# Aquila-2018-Under.net
KiCad netlist of a schematic drawn in EAGLE
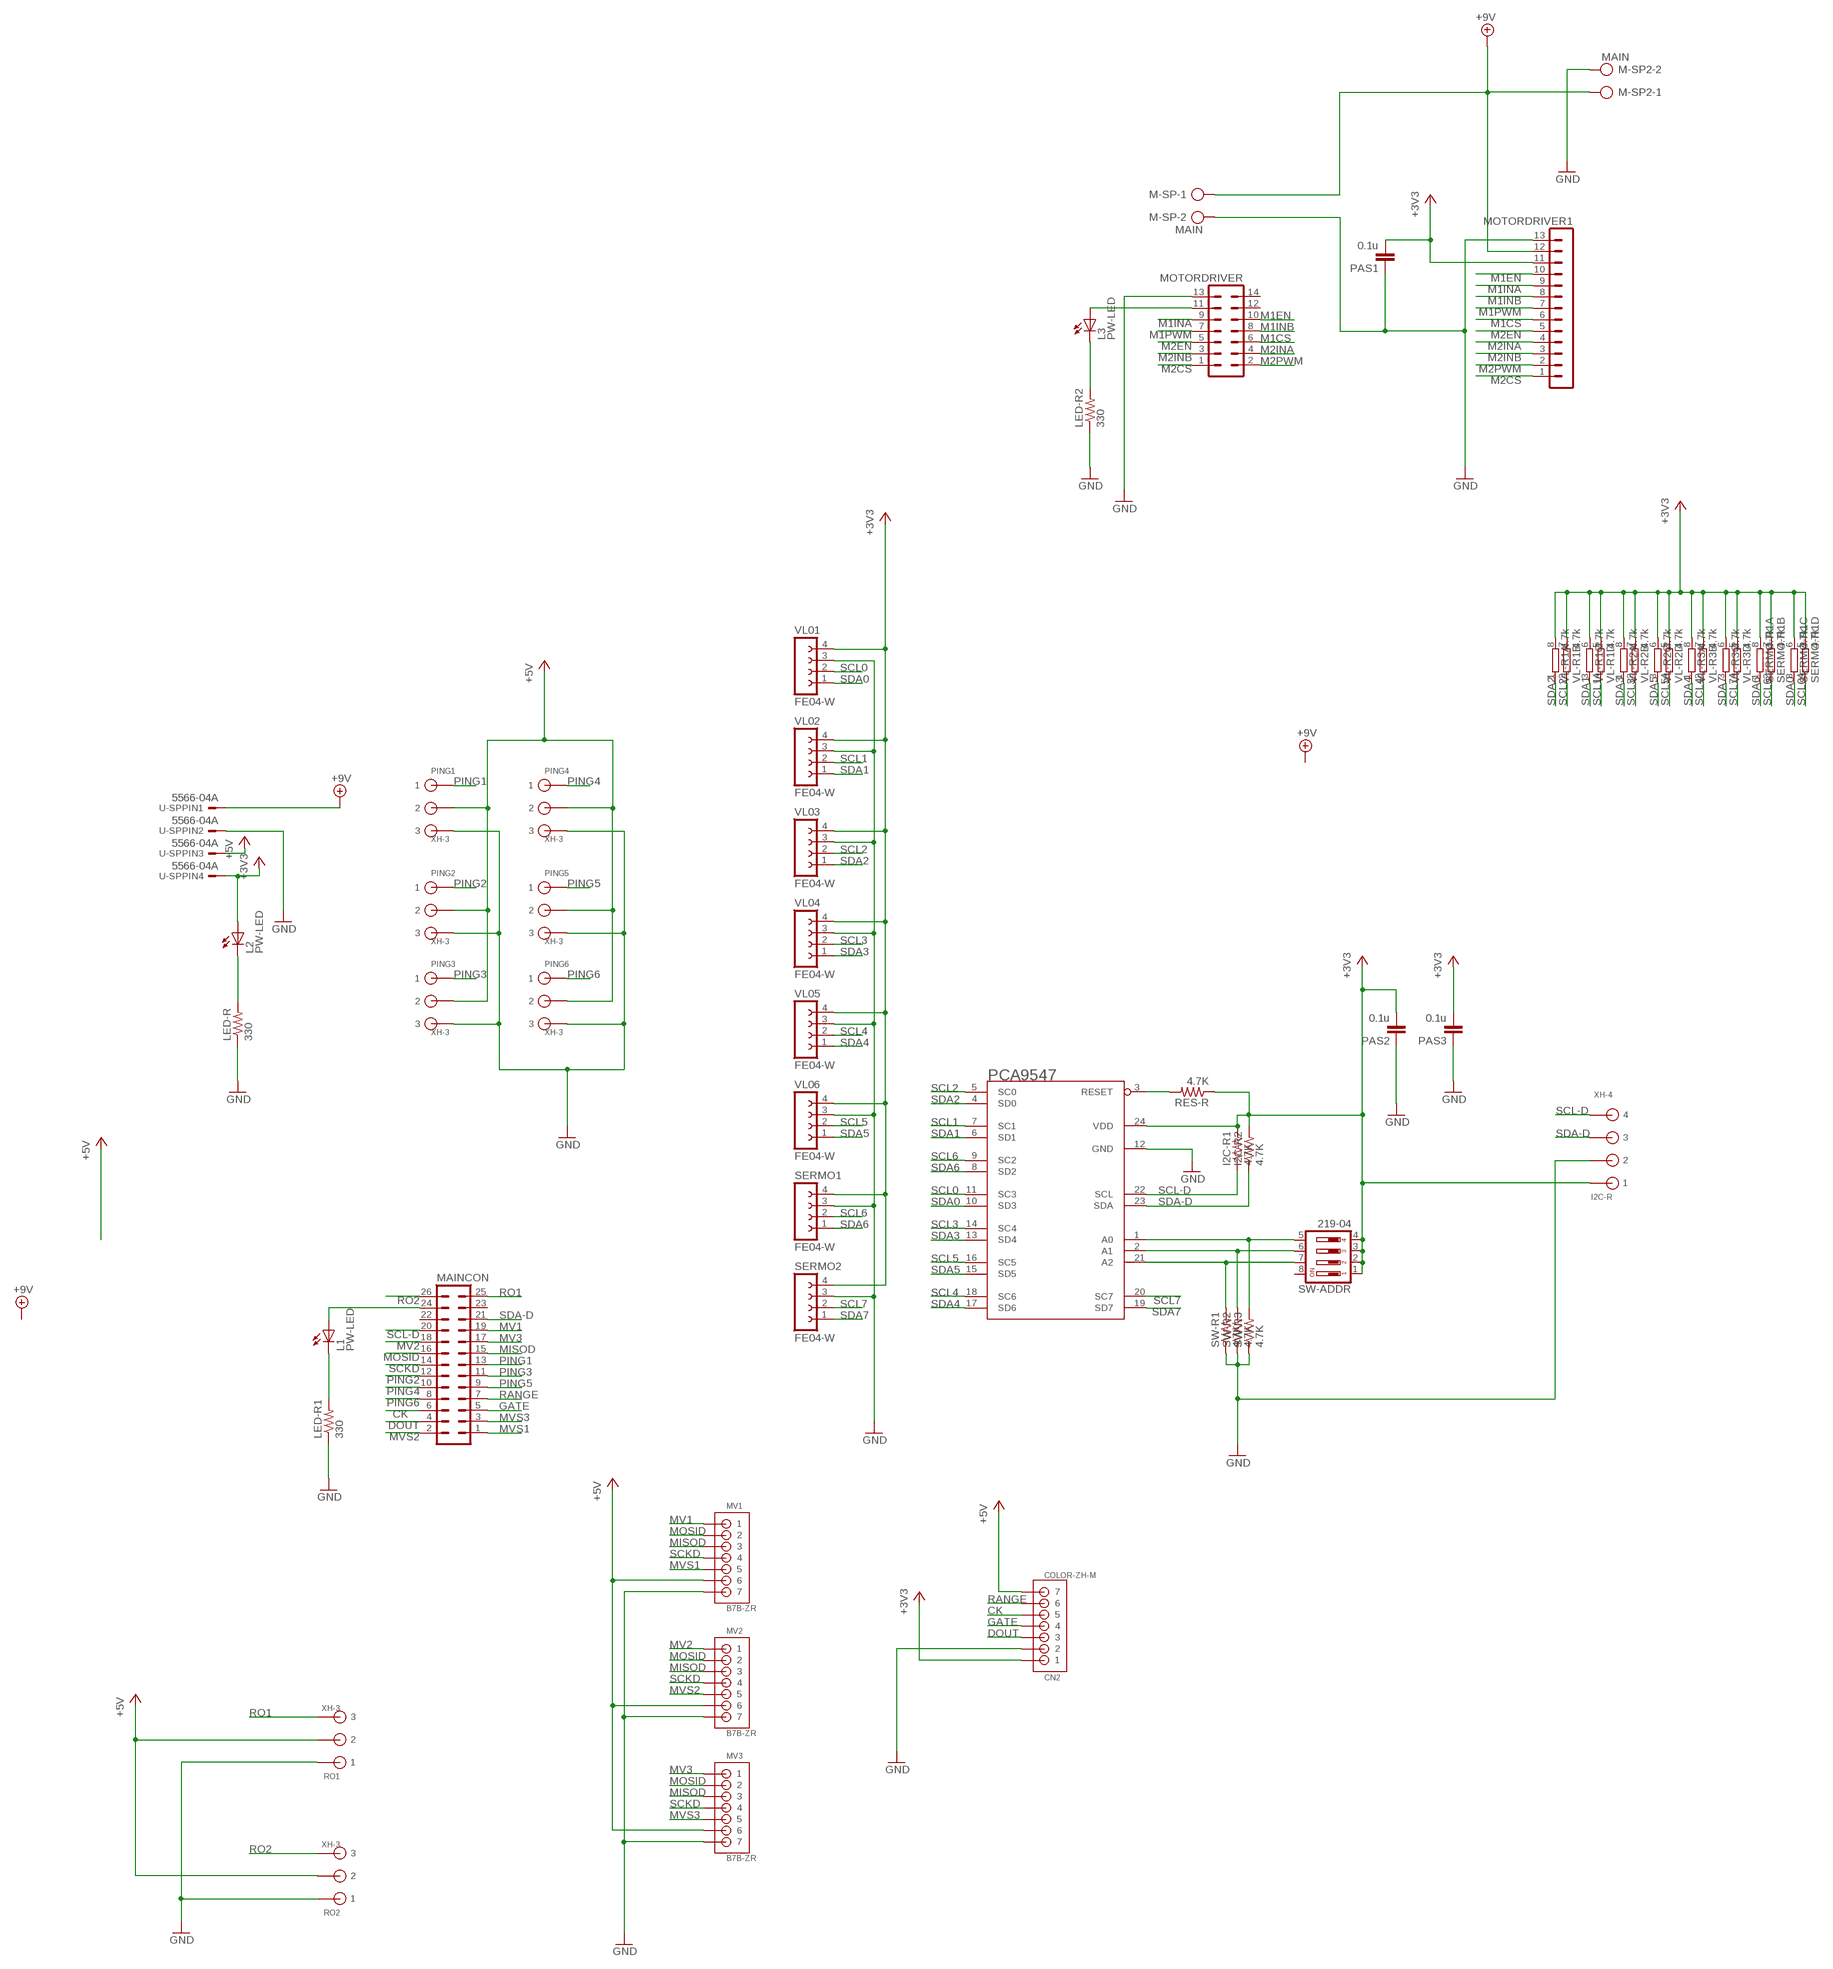
[diagram p0: schematic, sheet 1]

(export (version "E")
  (design (tool "Eeschema 10.0.6"))
  (components
    (comp (ref "CN2")
      (value "COLOR-ZH-M")
      (footprint "eagle-import:B7B-ZR")
      (libsource (lib "eagle-import") (part "B7B-ZR"))
    )
    (comp (ref "I2C-R")
      (value "XH-4")
      (footprint "eagle-import:CON4")
      (libsource (lib "eagle-import") (part "XH-4"))
    )
    (comp (ref "I2C-R1")
      (value "4.7K")
      (footprint "eagle-import:R0805")
      (libsource (lib "eagle-import") (part "R-US_R0805"))
    )
    (comp (ref "I2C-R2")
      (value "4.7K")
      (footprint "eagle-import:R0805")
      (libsource (lib "eagle-import") (part "R-US_R0805"))
    )
    (comp (ref "L1")
      (value "PW-LED")
      (footprint "eagle-import:CHIPLED_0805")
      (libsource (lib "eagle-import") (part "LEDCHIPLED_0805"))
    )
    (comp (ref "L2")
      (value "PW-LED")
      (footprint "eagle-import:CHIPLED_0805")
      (libsource (lib "eagle-import") (part "LEDCHIPLED_0805"))
    )
    (comp (ref "L3")
      (value "PW-LED")
      (footprint "eagle-import:CHIPLED_0805")
      (libsource (lib "eagle-import") (part "LEDCHIPLED_0805"))
    )
    (comp (ref "LED-R")
      (value "330")
      (footprint "eagle-import:R0805")
      (libsource (lib "eagle-import") (part "R-US_R0805"))
    )
    (comp (ref "LED-R1")
      (value "330")
      (footprint "eagle-import:R0805")
      (libsource (lib "eagle-import") (part "R-US_R0805"))
    )
    (comp (ref "LED-R2")
      (value "330")
      (footprint "eagle-import:R0805")
      (libsource (lib "eagle-import") (part "R-US_R0805"))
    )
    (comp (ref "M-SP")
      (value "MAIN")
      (footprint "eagle-import:AK500_2")
      (libsource (lib "eagle-import") (part "AK500/2"))
    )
    (comp (ref "M-SP2")
      (value "MAIN")
      (footprint "eagle-import:AK500_2")
      (libsource (lib "eagle-import") (part "AK500/2"))
    )
    (comp (ref "MAINCON")
      (value "ML26")
      (footprint "eagle-import:ML26")
      (libsource (lib "eagle-import") (part "ML26"))
    )
    (comp (ref "MOTORDRIVER")
      (value "ML14")
      (footprint "eagle-import:ML14")
      (libsource (lib "eagle-import") (part "ML14"))
    )
    (comp (ref "MOTORDRIVER1")
      (value "MA13-1")
      (footprint "eagle-import:MA13-1")
      (libsource (lib "eagle-import") (part "MA13-1"))
    )
    (comp (ref "MV1")
      (value "B7B-ZR")
      (footprint "eagle-import:B7B-ZR")
      (libsource (lib "eagle-import") (part "B7B-ZR"))
    )
    (comp (ref "MV2")
      (value "B7B-ZR")
      (footprint "eagle-import:B7B-ZR")
      (libsource (lib "eagle-import") (part "B7B-ZR"))
    )
    (comp (ref "MV3")
      (value "B7B-ZR")
      (footprint "eagle-import:B7B-ZR")
      (libsource (lib "eagle-import") (part "B7B-ZR"))
    )
    (comp (ref "PAS1")
      (value "0.1u")
      (footprint "eagle-import:C0805")
      (fields (field (name "SPICEPREFIX") "B"))
      (libsource (lib "eagle-import") (part "C-EUC0805"))
    )
    (comp (ref "PAS2")
      (value "0.1u")
      (footprint "eagle-import:C0805")
      (fields (field (name "SPICEPREFIX") "B"))
      (libsource (lib "eagle-import") (part "C-EUC0805"))
    )
    (comp (ref "PAS3")
      (value "0.1u")
      (footprint "eagle-import:C0805")
      (fields (field (name "SPICEPREFIX") "B"))
      (libsource (lib "eagle-import") (part "C-EUC0805"))
    )
    (comp (ref "PCA9547")
      (value "PCA9547")
      (footprint "eagle-import:SO24L")
      (libsource (lib "eagle-import") (part "PCA9547"))
    )
    (comp (ref "PING1")
      (value "XH-3")
      (footprint "eagle-import:CON3")
      (libsource (lib "eagle-import") (part "XH-3"))
    )
    (comp (ref "PING2")
      (value "XH-3")
      (footprint "eagle-import:CON3")
      (libsource (lib "eagle-import") (part "XH-3"))
    )
    (comp (ref "PING3")
      (value "XH-3")
      (footprint "eagle-import:CON3")
      (libsource (lib "eagle-import") (part "XH-3"))
    )
    (comp (ref "PING4")
      (value "XH-3")
      (footprint "eagle-import:CON3")
      (libsource (lib "eagle-import") (part "XH-3"))
    )
    (comp (ref "PING5")
      (value "XH-3")
      (footprint "eagle-import:CON3")
      (libsource (lib "eagle-import") (part "XH-3"))
    )
    (comp (ref "PING6")
      (value "XH-3")
      (footprint "eagle-import:CON3")
      (libsource (lib "eagle-import") (part "XH-3"))
    )
    (comp (ref "RES-R")
      (value "4.7K")
      (footprint "eagle-import:R0805")
      (libsource (lib "eagle-import") (part "R-US_R0805"))
    )
    (comp (ref "RO1")
      (value "XH-3")
      (footprint "eagle-import:CON3")
      (libsource (lib "eagle-import") (part "forprint_XH-3"))
    )
    (comp (ref "RO2")
      (value "XH-3")
      (footprint "eagle-import:CON3")
      (libsource (lib "eagle-import") (part "forprint_XH-3"))
    )
    (comp (ref "SERMO-R1")
      (value "4.7k")
      (footprint "eagle-import:EXB28V")
      (libsource (lib "eagle-import") (part "4R-NEXB28V"))
    )
    (comp (ref "SERMO1")
      (value "FE04-W")
      (footprint "eagle-import:FE04-W")
      (libsource (lib "eagle-import") (part "FE04-W"))
    )
    (comp (ref "SERMO2")
      (value "FE04-W")
      (footprint "eagle-import:FE04-W")
      (libsource (lib "eagle-import") (part "FE04-W"))
    )
    (comp (ref "SW-ADDR")
      (value "219-04")
      (footprint "eagle-import:CTS-219-04")
      (libsource (lib "eagle-import") (part "219-04"))
    )
    (comp (ref "SW-R1")
      (value "4.7K")
      (footprint "eagle-import:R0805")
      (libsource (lib "eagle-import") (part "R-US_R0805"))
    )
    (comp (ref "SW-R2")
      (value "4.7K")
      (footprint "eagle-import:R0805")
      (libsource (lib "eagle-import") (part "R-US_R0805"))
    )
    (comp (ref "SW-R3")
      (value "4.7K")
      (footprint "eagle-import:R0805")
      (libsource (lib "eagle-import") (part "R-US_R0805"))
    )
    (comp (ref "U-SP")
      (value "5566-04A")
      (footprint "eagle-import:5566-04A")
      (libsource (lib "eagle-import") (part "5566-04A"))
    )
    (comp (ref "VL-R1")
      (value "4.7k")
      (footprint "eagle-import:EXB28V")
      (libsource (lib "eagle-import") (part "4R-NEXB28V"))
    )
    (comp (ref "VL-R2")
      (value "4.7k")
      (footprint "eagle-import:EXB28V")
      (libsource (lib "eagle-import") (part "4R-NEXB28V"))
    )
    (comp (ref "VL-R3")
      (value "4.7k")
      (footprint "eagle-import:EXB28V")
      (libsource (lib "eagle-import") (part "4R-NEXB28V"))
    )
    (comp (ref "VL01")
      (value "FE04-W")
      (footprint "eagle-import:FE04-W")
      (libsource (lib "eagle-import") (part "FE04-W"))
    )
    (comp (ref "VL02")
      (value "FE04-W")
      (footprint "eagle-import:FE04-W")
      (libsource (lib "eagle-import") (part "FE04-W"))
    )
    (comp (ref "VL03")
      (value "FE04-W")
      (footprint "eagle-import:FE04-W")
      (libsource (lib "eagle-import") (part "FE04-W"))
    )
    (comp (ref "VL04")
      (value "FE04-W")
      (footprint "eagle-import:FE04-W")
      (libsource (lib "eagle-import") (part "FE04-W"))
    )
    (comp (ref "VL05")
      (value "FE04-W")
      (footprint "eagle-import:FE04-W")
      (libsource (lib "eagle-import") (part "FE04-W"))
    )
    (comp (ref "VL06")
      (value "FE04-W")
      (footprint "eagle-import:FE04-W")
      (libsource (lib "eagle-import") (part "FE04-W"))
    )
  )
  (nets
    (net (code "1") (name "+3V3") (class "Default")
      (node (ref "CN2") (pin "1") (pinfunction "1_1") (pintype "bidirectional"))
      (node (ref "I2C-R") (pin "P$1") (pinfunction "1_P$1") (pintype "bidirectional"))
      (node (ref "I2C-R1") (pin "2") (pinfunction "2_2") (pintype "passive"))
      (node (ref "I2C-R2") (pin "2") (pinfunction "2_2") (pintype "passive"))
      (node (ref "L2") (pin "A") (pinfunction "A_A") (pintype "passive"))
      (node (ref "MOTORDRIVER1") (pin "11") (pinfunction "11_11") (pintype "passive"))
      (node (ref "PAS1") (pin "2") (pinfunction "2_2") (pintype "passive"))
      (node (ref "PAS2") (pin "2") (pinfunction "2_2") (pintype "passive"))
      (node (ref "PAS3") (pin "2") (pinfunction "2_2") (pintype "passive"))
      (node (ref "PCA9547") (pin "24") (pinfunction "VDD_24") (pintype "power_in"))
      (node (ref "RES-R") (pin "1") (pinfunction "1_1") (pintype "passive"))
      (node (ref "SERMO-R1") (pin "5") (pinfunction "2_5") (pintype "passive"))
      (node (ref "SERMO-R1") (pin "6") (pinfunction "2_6") (pintype "passive"))
      (node (ref "SERMO-R1") (pin "7") (pinfunction "2_7") (pintype "passive"))
      (node (ref "SERMO-R1") (pin "8") (pinfunction "2_8") (pintype "passive"))
      (node (ref "SERMO1") (pin "4") (pinfunction "4_4") (pintype "passive"))
      (node (ref "SERMO2") (pin "4") (pinfunction "4_4") (pintype "passive"))
      (node (ref "SW-ADDR") (pin "1") (pinfunction "1_1") (pintype "passive"))
      (node (ref "SW-ADDR") (pin "2") (pinfunction "2_2") (pintype "passive"))
      (node (ref "SW-ADDR") (pin "3") (pinfunction "3_3") (pintype "passive"))
      (node (ref "SW-ADDR") (pin "4") (pinfunction "4_4") (pintype "passive"))
      (node (ref "U-SP") (pin "4") (pinfunction "S_4") (pintype "passive"))
      (node (ref "VL-R1") (pin "5") (pinfunction "2_5") (pintype "passive"))
      (node (ref "VL-R1") (pin "6") (pinfunction "2_6") (pintype "passive"))
      (node (ref "VL-R1") (pin "7") (pinfunction "2_7") (pintype "passive"))
      (node (ref "VL-R1") (pin "8") (pinfunction "2_8") (pintype "passive"))
      (node (ref "VL-R2") (pin "5") (pinfunction "2_5") (pintype "passive"))
      (node (ref "VL-R2") (pin "6") (pinfunction "2_6") (pintype "passive"))
      (node (ref "VL-R2") (pin "7") (pinfunction "2_7") (pintype "passive"))
      (node (ref "VL-R2") (pin "8") (pinfunction "2_8") (pintype "passive"))
      (node (ref "VL-R3") (pin "5") (pinfunction "2_5") (pintype "passive"))
      (node (ref "VL-R3") (pin "6") (pinfunction "2_6") (pintype "passive"))
      (node (ref "VL-R3") (pin "7") (pinfunction "2_7") (pintype "passive"))
      (node (ref "VL-R3") (pin "8") (pinfunction "2_8") (pintype "passive"))
      (node (ref "VL01") (pin "4") (pinfunction "4_4") (pintype "passive"))
      (node (ref "VL02") (pin "4") (pinfunction "4_4") (pintype "passive"))
      (node (ref "VL03") (pin "4") (pinfunction "4_4") (pintype "passive"))
      (node (ref "VL04") (pin "4") (pinfunction "4_4") (pintype "passive"))
      (node (ref "VL05") (pin "4") (pinfunction "4_4") (pintype "passive"))
      (node (ref "VL06") (pin "4") (pinfunction "4_4") (pintype "passive"))
    )
    (net (code "2") (name "+5V") (class "Default")
      (node (ref "CN2") (pin "7") (pinfunction "7_7") (pintype "bidirectional"))
      (node (ref "MV1") (pin "6") (pinfunction "6_6") (pintype "bidirectional"))
      (node (ref "MV2") (pin "6") (pinfunction "6_6") (pintype "bidirectional"))
      (node (ref "MV3") (pin "6") (pinfunction "6_6") (pintype "bidirectional"))
      (node (ref "PING1") (pin "P$2") (pinfunction "2_P$2") (pintype "bidirectional"))
      (node (ref "PING2") (pin "P$2") (pinfunction "2_P$2") (pintype "bidirectional"))
      (node (ref "PING3") (pin "P$2") (pinfunction "2_P$2") (pintype "bidirectional"))
      (node (ref "PING4") (pin "P$2") (pinfunction "2_P$2") (pintype "bidirectional"))
      (node (ref "PING5") (pin "P$2") (pinfunction "2_P$2") (pintype "bidirectional"))
      (node (ref "PING6") (pin "P$2") (pinfunction "2_P$2") (pintype "bidirectional"))
      (node (ref "RO1") (pin "P$2") (pinfunction "2_P$2") (pintype "bidirectional"))
      (node (ref "RO2") (pin "P$2") (pinfunction "2_P$2") (pintype "bidirectional"))
      (node (ref "U-SP") (pin "3") (pinfunction "S_3") (pintype "passive"))
    )
    (net (code "3") (name "+9V") (class "Default")
      (node (ref "M-SP") (pin "1") (pinfunction "KL_1") (pintype "passive"))
      (node (ref "M-SP2") (pin "1") (pinfunction "KL_1") (pintype "passive"))
      (node (ref "MOTORDRIVER1") (pin "12") (pinfunction "12_12") (pintype "passive"))
      (node (ref "U-SP") (pin "1") (pinfunction "S_1") (pintype "passive"))
    )
    (net (code "4") (name "/CK") (class "Default")
      (node (ref "CN2") (pin "5") (pinfunction "5_5") (pintype "bidirectional"))
      (node (ref "MAINCON") (pin "6") (pinfunction "6_6") (pintype "passive"))
    )
    (net (code "5") (name "/DOUT") (class "Default")
      (node (ref "CN2") (pin "3") (pinfunction "3_3") (pintype "bidirectional"))
      (node (ref "MAINCON") (pin "4") (pinfunction "4_4") (pintype "passive"))
    )
    (net (code "6") (name "/GATE") (class "Default")
      (node (ref "CN2") (pin "4") (pinfunction "4_4") (pintype "bidirectional"))
      (node (ref "MAINCON") (pin "5") (pinfunction "5_5") (pintype "passive"))
    )
    (net (code "7") (name "/M1CS") (class "Default")
      (node (ref "MOTORDRIVER") (pin "6") (pinfunction "6_6") (pintype "passive"))
      (node (ref "MOTORDRIVER1") (pin "6") (pinfunction "6_6") (pintype "passive"))
    )
    (net (code "8") (name "/M1EN") (class "Default")
      (node (ref "MOTORDRIVER") (pin "10") (pinfunction "10_10") (pintype "passive"))
      (node (ref "MOTORDRIVER1") (pin "10") (pinfunction "10_10") (pintype "passive"))
    )
    (net (code "9") (name "/M1INA") (class "Default")
      (node (ref "MOTORDRIVER") (pin "9") (pinfunction "9_9") (pintype "passive"))
      (node (ref "MOTORDRIVER1") (pin "9") (pinfunction "9_9") (pintype "passive"))
    )
    (net (code "10") (name "/M1INB") (class "Default")
      (node (ref "MOTORDRIVER") (pin "8") (pinfunction "8_8") (pintype "passive"))
      (node (ref "MOTORDRIVER1") (pin "8") (pinfunction "8_8") (pintype "passive"))
    )
    (net (code "11") (name "/M1PWM") (class "Default")
      (node (ref "MOTORDRIVER") (pin "7") (pinfunction "7_7") (pintype "passive"))
      (node (ref "MOTORDRIVER1") (pin "7") (pinfunction "7_7") (pintype "passive"))
    )
    (net (code "12") (name "/M2CS") (class "Default")
      (node (ref "MOTORDRIVER") (pin "1") (pinfunction "1_1") (pintype "passive"))
      (node (ref "MOTORDRIVER1") (pin "1") (pinfunction "1_1") (pintype "passive"))
    )
    (net (code "13") (name "/M2EN") (class "Default")
      (node (ref "MOTORDRIVER") (pin "5") (pinfunction "5_5") (pintype "passive"))
      (node (ref "MOTORDRIVER1") (pin "5") (pinfunction "5_5") (pintype "passive"))
    )
    (net (code "14") (name "/M2INA") (class "Default")
      (node (ref "MOTORDRIVER") (pin "4") (pinfunction "4_4") (pintype "passive"))
      (node (ref "MOTORDRIVER1") (pin "4") (pinfunction "4_4") (pintype "passive"))
    )
    (net (code "15") (name "/M2INB") (class "Default")
      (node (ref "MOTORDRIVER") (pin "3") (pinfunction "3_3") (pintype "passive"))
      (node (ref "MOTORDRIVER1") (pin "3") (pinfunction "3_3") (pintype "passive"))
    )
    (net (code "16") (name "/M2PWM") (class "Default")
      (node (ref "MOTORDRIVER") (pin "2") (pinfunction "2_2") (pintype "passive"))
      (node (ref "MOTORDRIVER1") (pin "2") (pinfunction "2_2") (pintype "passive"))
    )
    (net (code "17") (name "/MISOD") (class "Default")
      (node (ref "MAINCON") (pin "15") (pinfunction "15_15") (pintype "passive"))
      (node (ref "MV1") (pin "3") (pinfunction "3_3") (pintype "bidirectional"))
      (node (ref "MV2") (pin "3") (pinfunction "3_3") (pintype "bidirectional"))
      (node (ref "MV3") (pin "3") (pinfunction "3_3") (pintype "bidirectional"))
    )
    (net (code "18") (name "/MOSID") (class "Default")
      (node (ref "MAINCON") (pin "16") (pinfunction "16_16") (pintype "passive"))
      (node (ref "MV1") (pin "2") (pinfunction "2_2") (pintype "bidirectional"))
      (node (ref "MV2") (pin "2") (pinfunction "2_2") (pintype "bidirectional"))
      (node (ref "MV3") (pin "2") (pinfunction "2_2") (pintype "bidirectional"))
    )
    (net (code "19") (name "/MV1") (class "Default")
      (node (ref "MAINCON") (pin "19") (pinfunction "19_19") (pintype "passive"))
      (node (ref "MV1") (pin "1") (pinfunction "1_1") (pintype "bidirectional"))
    )
    (net (code "20") (name "/MV2") (class "Default")
      (node (ref "MAINCON") (pin "18") (pinfunction "18_18") (pintype "passive"))
      (node (ref "MV2") (pin "1") (pinfunction "1_1") (pintype "bidirectional"))
    )
    (net (code "21") (name "/MV3") (class "Default")
      (node (ref "MAINCON") (pin "17") (pinfunction "17_17") (pintype "passive"))
      (node (ref "MV3") (pin "1") (pinfunction "1_1") (pintype "bidirectional"))
    )
    (net (code "22") (name "/MVS1") (class "Default")
      (node (ref "MAINCON") (pin "1") (pinfunction "1_1") (pintype "passive"))
      (node (ref "MV1") (pin "5") (pinfunction "5_5") (pintype "bidirectional"))
    )
    (net (code "23") (name "/MVS2") (class "Default")
      (node (ref "MAINCON") (pin "2") (pinfunction "2_2") (pintype "passive"))
      (node (ref "MV2") (pin "5") (pinfunction "5_5") (pintype "bidirectional"))
    )
    (net (code "24") (name "/MVS3") (class "Default")
      (node (ref "MAINCON") (pin "3") (pinfunction "3_3") (pintype "passive"))
      (node (ref "MV3") (pin "5") (pinfunction "5_5") (pintype "bidirectional"))
    )
    (net (code "25") (name "/PING1") (class "Default")
      (node (ref "MAINCON") (pin "13") (pinfunction "13_13") (pintype "passive"))
      (node (ref "PING1") (pin "P$1") (pinfunction "1_P$1") (pintype "bidirectional"))
    )
    (net (code "26") (name "/PING2") (class "Default")
      (node (ref "MAINCON") (pin "12") (pinfunction "12_12") (pintype "passive"))
      (node (ref "PING2") (pin "P$1") (pinfunction "1_P$1") (pintype "bidirectional"))
    )
    (net (code "27") (name "/PING3") (class "Default")
      (node (ref "MAINCON") (pin "11") (pinfunction "11_11") (pintype "passive"))
      (node (ref "PING3") (pin "P$1") (pinfunction "1_P$1") (pintype "bidirectional"))
    )
    (net (code "28") (name "/PING4") (class "Default")
      (node (ref "MAINCON") (pin "10") (pinfunction "10_10") (pintype "passive"))
      (node (ref "PING4") (pin "P$1") (pinfunction "1_P$1") (pintype "bidirectional"))
    )
    (net (code "29") (name "/PING5") (class "Default")
      (node (ref "MAINCON") (pin "9") (pinfunction "9_9") (pintype "passive"))
      (node (ref "PING5") (pin "P$1") (pinfunction "1_P$1") (pintype "bidirectional"))
    )
    (net (code "30") (name "/PING6") (class "Default")
      (node (ref "MAINCON") (pin "8") (pinfunction "8_8") (pintype "passive"))
      (node (ref "PING6") (pin "P$1") (pinfunction "1_P$1") (pintype "bidirectional"))
    )
    (net (code "31") (name "/RANGE") (class "Default")
      (node (ref "CN2") (pin "6") (pinfunction "6_6") (pintype "bidirectional"))
      (node (ref "MAINCON") (pin "7") (pinfunction "7_7") (pintype "passive"))
    )
    (net (code "32") (name "/RO1") (class "Default")
      (node (ref "MAINCON") (pin "25") (pinfunction "25_25") (pintype "passive"))
      (node (ref "RO1") (pin "P$3") (pinfunction "3_P$3") (pintype "bidirectional"))
    )
    (net (code "33") (name "/RO2") (class "Default")
      (node (ref "MAINCON") (pin "26") (pinfunction "26_26") (pintype "passive"))
      (node (ref "RO2") (pin "P$3") (pinfunction "3_P$3") (pintype "bidirectional"))
    )
    (net (code "34") (name "/SCKD") (class "Default")
      (node (ref "MAINCON") (pin "14") (pinfunction "14_14") (pintype "passive"))
      (node (ref "MV1") (pin "4") (pinfunction "4_4") (pintype "bidirectional"))
      (node (ref "MV2") (pin "4") (pinfunction "4_4") (pintype "bidirectional"))
      (node (ref "MV3") (pin "4") (pinfunction "4_4") (pintype "bidirectional"))
    )
    (net (code "35") (name "/SCL-D") (class "Default")
      (node (ref "I2C-R") (pin "P$4") (pinfunction "4_P$4") (pintype "bidirectional"))
      (node (ref "I2C-R1") (pin "1") (pinfunction "1_1") (pintype "passive"))
      (node (ref "MAINCON") (pin "20") (pinfunction "20_20") (pintype "passive"))
      (node (ref "PCA9547") (pin "22") (pinfunction "SCL_22") (pintype "bidirectional"))
    )
    (net (code "36") (name "/SCL0") (class "Default")
      (node (ref "PCA9547") (pin "11") (pinfunction "SC3_11") (pintype "bidirectional"))
      (node (ref "SERMO-R1") (pin "4") (pinfunction "1_4") (pintype "passive"))
      (node (ref "VL01") (pin "2") (pinfunction "2_2") (pintype "passive"))
    )
    (net (code "37") (name "/SCL1") (class "Default")
      (node (ref "PCA9547") (pin "7") (pinfunction "SC1_7") (pintype "bidirectional"))
      (node (ref "VL-R1") (pin "4") (pinfunction "1_4") (pintype "passive"))
      (node (ref "VL02") (pin "2") (pinfunction "2_2") (pintype "passive"))
    )
    (net (code "38") (name "/SCL2") (class "Default")
      (node (ref "PCA9547") (pin "5") (pinfunction "SC0_5") (pintype "bidirectional"))
      (node (ref "VL-R1") (pin "2") (pinfunction "1_2") (pintype "passive"))
      (node (ref "VL03") (pin "2") (pinfunction "2_2") (pintype "passive"))
    )
    (net (code "39") (name "/SCL3") (class "Default")
      (node (ref "PCA9547") (pin "14") (pinfunction "SC4_14") (pintype "bidirectional"))
      (node (ref "VL-R2") (pin "2") (pinfunction "1_2") (pintype "passive"))
      (node (ref "VL04") (pin "2") (pinfunction "2_2") (pintype "passive"))
    )
    (net (code "40") (name "/SCL4") (class "Default")
      (node (ref "PCA9547") (pin "18") (pinfunction "SC6_18") (pintype "bidirectional"))
      (node (ref "VL-R3") (pin "2") (pinfunction "1_2") (pintype "passive"))
      (node (ref "VL05") (pin "2") (pinfunction "2_2") (pintype "passive"))
    )
    (net (code "41") (name "/SCL5") (class "Default")
      (node (ref "PCA9547") (pin "16") (pinfunction "SC5_16") (pintype "bidirectional"))
      (node (ref "VL-R2") (pin "4") (pinfunction "1_4") (pintype "passive"))
      (node (ref "VL06") (pin "2") (pinfunction "2_2") (pintype "passive"))
    )
    (net (code "42") (name "/SCL6") (class "Default")
      (node (ref "PCA9547") (pin "9") (pinfunction "SC2_9") (pintype "bidirectional"))
      (node (ref "SERMO-R1") (pin "2") (pinfunction "1_2") (pintype "passive"))
      (node (ref "SERMO1") (pin "2") (pinfunction "2_2") (pintype "passive"))
    )
    (net (code "43") (name "/SCL7") (class "Default")
      (node (ref "PCA9547") (pin "20") (pinfunction "SC7_20") (pintype "bidirectional"))
      (node (ref "SERMO2") (pin "2") (pinfunction "2_2") (pintype "passive"))
      (node (ref "VL-R3") (pin "4") (pinfunction "1_4") (pintype "passive"))
    )
    (net (code "44") (name "/SDA-D") (class "Default")
      (node (ref "I2C-R") (pin "P$3") (pinfunction "3_P$3") (pintype "bidirectional"))
      (node (ref "I2C-R2") (pin "1") (pinfunction "1_1") (pintype "passive"))
      (node (ref "MAINCON") (pin "21") (pinfunction "21_21") (pintype "passive"))
      (node (ref "PCA9547") (pin "23") (pinfunction "SDA_23") (pintype "bidirectional"))
    )
    (net (code "45") (name "/SDA0") (class "Default")
      (node (ref "PCA9547") (pin "10") (pinfunction "SD3_10") (pintype "bidirectional"))
      (node (ref "SERMO-R1") (pin "3") (pinfunction "1_3") (pintype "passive"))
      (node (ref "VL01") (pin "1") (pinfunction "1_1") (pintype "passive"))
    )
    (net (code "46") (name "/SDA1") (class "Default")
      (node (ref "PCA9547") (pin "6") (pinfunction "SD1_6") (pintype "bidirectional"))
      (node (ref "VL-R1") (pin "3") (pinfunction "1_3") (pintype "passive"))
      (node (ref "VL02") (pin "1") (pinfunction "1_1") (pintype "passive"))
    )
    (net (code "47") (name "/SDA2") (class "Default")
      (node (ref "PCA9547") (pin "4") (pinfunction "SD0_4") (pintype "bidirectional"))
      (node (ref "VL-R1") (pin "1") (pinfunction "1_1") (pintype "passive"))
      (node (ref "VL03") (pin "1") (pinfunction "1_1") (pintype "passive"))
    )
    (net (code "48") (name "/SDA3") (class "Default")
      (node (ref "PCA9547") (pin "13") (pinfunction "SD4_13") (pintype "bidirectional"))
      (node (ref "VL-R2") (pin "1") (pinfunction "1_1") (pintype "passive"))
      (node (ref "VL04") (pin "1") (pinfunction "1_1") (pintype "passive"))
    )
    (net (code "49") (name "/SDA4") (class "Default")
      (node (ref "PCA9547") (pin "17") (pinfunction "SD6_17") (pintype "bidirectional"))
      (node (ref "VL-R3") (pin "1") (pinfunction "1_1") (pintype "passive"))
      (node (ref "VL05") (pin "1") (pinfunction "1_1") (pintype "passive"))
    )
    (net (code "50") (name "/SDA5") (class "Default")
      (node (ref "PCA9547") (pin "15") (pinfunction "SD5_15") (pintype "bidirectional"))
      (node (ref "VL-R2") (pin "3") (pinfunction "1_3") (pintype "passive"))
      (node (ref "VL06") (pin "1") (pinfunction "1_1") (pintype "passive"))
    )
    (net (code "51") (name "/SDA6") (class "Default")
      (node (ref "PCA9547") (pin "8") (pinfunction "SD2_8") (pintype "bidirectional"))
      (node (ref "SERMO-R1") (pin "1") (pinfunction "1_1") (pintype "passive"))
      (node (ref "SERMO1") (pin "1") (pinfunction "1_1") (pintype "passive"))
    )
    (net (code "52") (name "/SDA7") (class "Default")
      (node (ref "PCA9547") (pin "19") (pinfunction "SD7_19") (pintype "bidirectional"))
      (node (ref "SERMO2") (pin "1") (pinfunction "1_1") (pintype "passive"))
      (node (ref "VL-R3") (pin "3") (pinfunction "1_3") (pintype "passive"))
    )
    (net (code "53") (name "GND") (class "Default")
      (node (ref "CN2") (pin "2") (pinfunction "2_2") (pintype "bidirectional"))
      (node (ref "I2C-R") (pin "P$2") (pinfunction "2_P$2") (pintype "bidirectional"))
      (node (ref "LED-R") (pin "1") (pinfunction "1_1") (pintype "passive"))
      (node (ref "LED-R1") (pin "1") (pinfunction "1_1") (pintype "passive"))
      (node (ref "LED-R2") (pin "1") (pinfunction "1_1") (pintype "passive"))
      (node (ref "M-SP") (pin "2") (pinfunction "KL_2") (pintype "passive"))
      (node (ref "M-SP2") (pin "2") (pinfunction "KL_2") (pintype "passive"))
      (node (ref "MOTORDRIVER") (pin "13") (pinfunction "13_13") (pintype "passive"))
      (node (ref "MOTORDRIVER1") (pin "13") (pinfunction "13_13") (pintype "passive"))
      (node (ref "MV1") (pin "7") (pinfunction "7_7") (pintype "bidirectional"))
      (node (ref "MV2") (pin "7") (pinfunction "7_7") (pintype "bidirectional"))
      (node (ref "MV3") (pin "7") (pinfunction "7_7") (pintype "bidirectional"))
      (node (ref "PAS1") (pin "1") (pinfunction "1_1") (pintype "passive"))
      (node (ref "PAS2") (pin "1") (pinfunction "1_1") (pintype "passive"))
      (node (ref "PAS3") (pin "1") (pinfunction "1_1") (pintype "passive"))
      (node (ref "PCA9547") (pin "12") (pinfunction "GND_12") (pintype "power_in"))
      (node (ref "PING1") (pin "P$3") (pinfunction "3_P$3") (pintype "bidirectional"))
      (node (ref "PING2") (pin "P$3") (pinfunction "3_P$3") (pintype "bidirectional"))
      (node (ref "PING3") (pin "P$3") (pinfunction "3_P$3") (pintype "bidirectional"))
      (node (ref "PING4") (pin "P$3") (pinfunction "3_P$3") (pintype "bidirectional"))
      (node (ref "PING5") (pin "P$3") (pinfunction "3_P$3") (pintype "bidirectional"))
      (node (ref "PING6") (pin "P$3") (pinfunction "3_P$3") (pintype "bidirectional"))
      (node (ref "RO1") (pin "P$1") (pinfunction "1_P$1") (pintype "bidirectional"))
      (node (ref "RO2") (pin "P$1") (pinfunction "1_P$1") (pintype "bidirectional"))
      (node (ref "SERMO1") (pin "3") (pinfunction "3_3") (pintype "passive"))
      (node (ref "SERMO2") (pin "3") (pinfunction "3_3") (pintype "passive"))
      (node (ref "SW-R1") (pin "1") (pinfunction "1_1") (pintype "passive"))
      (node (ref "SW-R2") (pin "1") (pinfunction "1_1") (pintype "passive"))
      (node (ref "SW-R3") (pin "1") (pinfunction "1_1") (pintype "passive"))
      (node (ref "U-SP") (pin "2") (pinfunction "S_2") (pintype "passive"))
      (node (ref "VL01") (pin "3") (pinfunction "3_3") (pintype "passive"))
      (node (ref "VL02") (pin "3") (pinfunction "3_3") (pintype "passive"))
      (node (ref "VL03") (pin "3") (pinfunction "3_3") (pintype "passive"))
      (node (ref "VL04") (pin "3") (pinfunction "3_3") (pintype "passive"))
      (node (ref "VL05") (pin "3") (pinfunction "3_3") (pintype "passive"))
      (node (ref "VL06") (pin "3") (pinfunction "3_3") (pintype "passive"))
    )
    (net (code "54") (name "Net-(L1-PadA)") (class "Default")
      (node (ref "L1") (pin "A") (pinfunction "A_A") (pintype "passive"))
      (node (ref "MAINCON") (pin "24") (pinfunction "24_24") (pintype "passive"))
    )
    (net (code "55") (name "Net-(L1-PadC)") (class "Default")
      (node (ref "L1") (pin "C") (pinfunction "C_C") (pintype "passive"))
      (node (ref "LED-R1") (pin "2") (pinfunction "2_2") (pintype "passive"))
    )
    (net (code "56") (name "Net-(L2-PadC)") (class "Default")
      (node (ref "L2") (pin "C") (pinfunction "C_C") (pintype "passive"))
      (node (ref "LED-R") (pin "2") (pinfunction "2_2") (pintype "passive"))
    )
    (net (code "57") (name "Net-(L3-PadA)") (class "Default")
      (node (ref "L3") (pin "A") (pinfunction "A_A") (pintype "passive"))
      (node (ref "MOTORDRIVER") (pin "11") (pinfunction "11_11") (pintype "passive"))
    )
    (net (code "58") (name "Net-(L3-PadC)") (class "Default")
      (node (ref "L3") (pin "C") (pinfunction "C_C") (pintype "passive"))
      (node (ref "LED-R2") (pin "2") (pinfunction "2_2") (pintype "passive"))
    )
    (net (code "59") (name "Net-(PCA9547-A0)") (class "Default")
      (node (ref "PCA9547") (pin "1") (pinfunction "A0_1") (pintype "input"))
      (node (ref "SW-ADDR") (pin "5") (pinfunction "5_5") (pintype "passive"))
      (node (ref "SW-R3") (pin "2") (pinfunction "2_2") (pintype "passive"))
    )
    (net (code "60") (name "Net-(PCA9547-A1)") (class "Default")
      (node (ref "PCA9547") (pin "2") (pinfunction "A1_2") (pintype "input"))
      (node (ref "SW-ADDR") (pin "6") (pinfunction "6_6") (pintype "passive"))
      (node (ref "SW-R2") (pin "2") (pinfunction "2_2") (pintype "passive"))
    )
    (net (code "61") (name "Net-(PCA9547-A2)") (class "Default")
      (node (ref "PCA9547") (pin "21") (pinfunction "A2_21") (pintype "input"))
      (node (ref "SW-ADDR") (pin "7") (pinfunction "7_7") (pintype "passive"))
      (node (ref "SW-R1") (pin "2") (pinfunction "2_2") (pintype "passive"))
    )
    (net (code "62") (name "Net-(PCA9547-RESET)") (class "Default")
      (node (ref "PCA9547") (pin "3") (pinfunction "RESET_3") (pintype "bidirectional"))
      (node (ref "RES-R") (pin "2") (pinfunction "2_2") (pintype "passive"))
    )
    (net (code "63") (name "unconnected-(MAINCON-Pad22)") (class "Default")
      (node (ref "MAINCON") (pin "22") (pinfunction "22_22") (pintype "passive"))
    )
    (net (code "64") (name "unconnected-(MAINCON-Pad23)") (class "Default")
      (node (ref "MAINCON") (pin "23") (pinfunction "23_23") (pintype "passive"))
    )
    (net (code "65") (name "unconnected-(MOTORDRIVER-Pad12)") (class "Default")
      (node (ref "MOTORDRIVER") (pin "12") (pinfunction "12_12") (pintype "passive"))
    )
    (net (code "66") (name "unconnected-(MOTORDRIVER-Pad14)") (class "Default")
      (node (ref "MOTORDRIVER") (pin "14") (pinfunction "14_14") (pintype "passive"))
    )
    (net (code "67") (name "unconnected-(SW-ADDR-Pad8)") (class "Default")
      (node (ref "SW-ADDR") (pin "8") (pinfunction "8_8") (pintype "passive"))
    )
  )
)
